# Akuaphonic_All_FIX.net
KiCad netlist of a schematic drawn in EAGLE
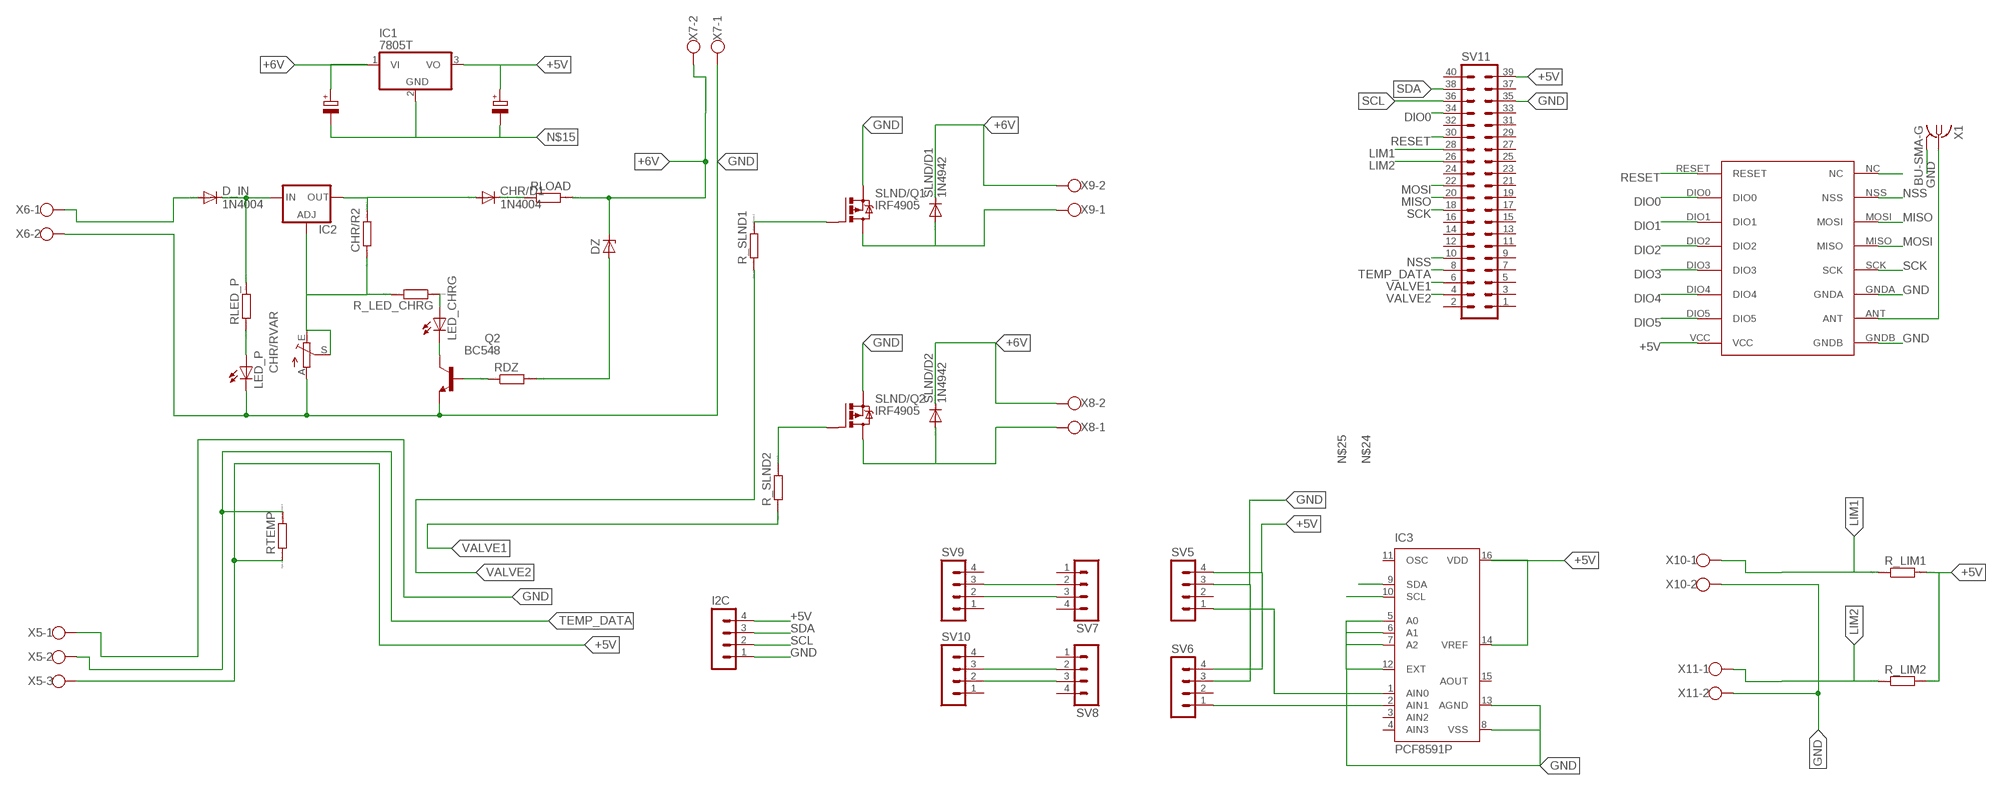
[diagram p0: schematic, sheet 1]

(export (version "E")
  (design (tool "Eeschema 10.0.6"))
  (components
    (comp (ref "CHR/D1")
      (value "1N4004")
      (footprint "eagle-import:DO41-10")
      (libsource (lib "eagle-import") (part "1N4004"))
    )
    (comp (ref "CHR/R2")
      (value "R0207/10")
      (footprint "eagle-import:0207_10")
      (libsource (lib "eagle-import") (part "R0207/10"))
    )
    (comp (ref "CHR/RVAR")
      (value "TRIM_EU-B25P")
      (footprint "eagle-import:B25P")
      (libsource (lib "eagle-import") (part "TRIM_EU-B25P"))
    )
    (comp (ref "DZ")
      (value "ZENER-DIODEDO35Z10")
      (footprint "eagle-import:DO35Z10")
      (libsource (lib "eagle-import") (part "ZENER-DIODEDO35Z10"))
    )
    (comp (ref "D_IN")
      (value "1N4004")
      (footprint "eagle-import:DO41-10")
      (libsource (lib "eagle-import") (part "1N4004"))
    )
    (comp (ref "I2C")
      (value "MA04-1")
      (footprint "eagle-import:MA04-1")
      (libsource (lib "eagle-import") (part "MA04-1"))
    )
    (comp (ref "IC1")
      (value "7805T")
      (footprint "eagle-import:TO220H")
      (libsource (lib "eagle-import") (part "78T05"))
    )
    (comp (ref "IC2")
      (value "LM317TL")
      (footprint "eagle-import:317TL")
      (libsource (lib "eagle-import") (part "LM317TL"))
    )
    (comp (ref "IC3")
      (value "PCF8591P")
      (footprint "eagle-import:DIL16")
      (fields (field (name "MF") "FARNELL"))
      (libsource (lib "eagle-import") (part "PCF8591P"))
    )
    (comp (ref "LED_CHRG")
      (value "LED3MM")
      (footprint "eagle-import:LED3MM")
      (libsource (lib "eagle-import") (part "LED3MM"))
    )
    (comp (ref "LED_P")
      (value "LED3MM")
      (footprint "eagle-import:LED3MM")
      (libsource (lib "eagle-import") (part "LED3MM"))
    )
    (comp (ref "Q2")
      (value "BC548")
      (footprint "eagle-import:TO92-EBC")
      (libsource (lib "eagle-import") (part "BC548"))
    )
    (comp (ref "RDZ")
      (value "R0207/10")
      (footprint "eagle-import:0207_10")
      (libsource (lib "eagle-import") (part "R0207/10"))
    )
    (comp (ref "RLED_P")
      (value "R0207/10")
      (footprint "eagle-import:0207_10")
      (libsource (lib "eagle-import") (part "R0207/10"))
    )
    (comp (ref "RLOAD")
      (value "R0207/10")
      (footprint "eagle-import:0207_10")
      (libsource (lib "eagle-import") (part "R0207/10"))
    )
    (comp (ref "RTEMP")
      (value "R0207/10")
      (footprint "eagle-import:0207_10")
      (libsource (lib "eagle-import") (part "R0207/10"))
    )
    (comp (ref "R_LED_CHRG")
      (value "R0207/10")
      (footprint "eagle-import:0207_10")
      (libsource (lib "eagle-import") (part "R0207/10"))
    )
    (comp (ref "R_LIM1")
      (value "R0207/10")
      (footprint "eagle-import:0207_10")
      (libsource (lib "eagle-import") (part "R0207/10"))
    )
    (comp (ref "R_LIM2")
      (value "R0207/10")
      (footprint "eagle-import:0207_10")
      (libsource (lib "eagle-import") (part "R0207/10"))
    )
    (comp (ref "R_SLND1")
      (value "R0207/10")
      (footprint "eagle-import:0207_10")
      (libsource (lib "eagle-import") (part "R0207/10"))
    )
    (comp (ref "R_SLND2")
      (value "R0207/10")
      (footprint "eagle-import:0207_10")
      (libsource (lib "eagle-import") (part "R0207/10"))
    )
    (comp (ref "SLND/D1")
      (value "1N4942")
      (footprint "eagle-import:DO41-10")
      (libsource (lib "eagle-import") (part "1N4942"))
    )
    (comp (ref "SLND/D2")
      (value "1N4942")
      (footprint "eagle-import:DO41-10")
      (libsource (lib "eagle-import") (part "1N4942"))
    )
    (comp (ref "SLND/Q1")
      (value "IRF4905")
      (footprint "eagle-import:TO220BH")
      (libsource (lib "eagle-import") (part "IRF4905"))
    )
    (comp (ref "SLND/Q2")
      (value "IRF4905")
      (footprint "eagle-import:TO220BH")
      (libsource (lib "eagle-import") (part "IRF4905"))
    )
    (comp (ref "SV5")
      (value "MA04-1")
      (footprint "eagle-import:MA04-1")
      (libsource (lib "eagle-import") (part "MA04-1"))
    )
    (comp (ref "SV6")
      (value "MA04-1")
      (footprint "eagle-import:MA04-1")
      (libsource (lib "eagle-import") (part "MA04-1"))
    )
    (comp (ref "SV7")
      (value "MA04-1")
      (footprint "eagle-import:MA04-1")
      (libsource (lib "eagle-import") (part "MA04-1"))
    )
    (comp (ref "SV8")
      (value "MA04-1")
      (footprint "eagle-import:MA04-1")
      (libsource (lib "eagle-import") (part "MA04-1"))
    )
    (comp (ref "SV9")
      (value "MA04-1")
      (footprint "eagle-import:MA04-1")
      (libsource (lib "eagle-import") (part "MA04-1"))
    )
    (comp (ref "SV10")
      (value "MA04-1")
      (footprint "eagle-import:MA04-1")
      (libsource (lib "eagle-import") (part "MA04-1"))
    )
    (comp (ref "SV11")
      (value "MA20-2")
      (footprint "eagle-import:MA20-2")
      (libsource (lib "eagle-import") (part "MA20-2"))
    )
    (comp (ref "U$1")
      (value "RFM69HW")
      (footprint "eagle-import:RFM")
      (libsource (lib "eagle-import") (part "RFM69HW"))
    )
    (comp (ref "X1")
      (value "BU-SMA-G")
      (footprint "eagle-import:BU-SMA-G")
      (libsource (lib "eagle-import") (part "BU-SMA-G"))
    )
    (comp (ref "X5")
      (value "W237-103")
      (footprint "eagle-import:W237-103")
      (fields (field (name "MPN") "237-103"))
      (libsource (lib "eagle-import") (part "W237-103"))
    )
    (comp (ref "X6")
      (value "W237-102")
      (footprint "eagle-import:W237-102")
      (fields (field (name "MPN") "237-102"))
      (libsource (lib "eagle-import") (part "W237-102"))
    )
    (comp (ref "X7")
      (value "W237-102")
      (footprint "eagle-import:W237-102")
      (fields (field (name "MPN") "237-102"))
      (libsource (lib "eagle-import") (part "W237-102"))
    )
    (comp (ref "X8")
      (value "W237-102")
      (footprint "eagle-import:W237-102")
      (fields (field (name "MPN") "237-102"))
      (libsource (lib "eagle-import") (part "W237-102"))
    )
    (comp (ref "X9")
      (value "W237-102")
      (footprint "eagle-import:W237-102")
      (fields (field (name "MPN") "237-102"))
      (libsource (lib "eagle-import") (part "W237-102"))
    )
    (comp (ref "X10")
      (value "W237-102")
      (footprint "eagle-import:W237-102")
      (fields (field (name "MPN") "237-102"))
      (libsource (lib "eagle-import") (part "W237-102"))
    )
    (comp (ref "X11")
      (value "W237-102")
      (footprint "eagle-import:W237-102")
      (fields (field (name "MPN") "237-102"))
      (libsource (lib "eagle-import") (part "W237-102"))
    )
  )
  (nets
    (net (code "1") (name "+5V") (class "Default")
      (node (ref "I2C") (pin "4") (pinfunction "4_4") (pintype "passive"))
      (node (ref "IC1") (pin "3") (pinfunction "VO_3") (pintype "passive"))
      (node (ref "IC3") (pin "14") (pinfunction "VREF_14") (pintype "input"))
      (node (ref "IC3") (pin "16") (pinfunction "VDD_16") (pintype "power_in"))
      (node (ref "RTEMP") (pin "1") (pinfunction "1_1") (pintype "passive"))
      (node (ref "R_LIM1") (pin "2") (pinfunction "2_2") (pintype "passive"))
      (node (ref "R_LIM2") (pin "2") (pinfunction "2_2") (pintype "passive"))
      (node (ref "SV11") (pin "39") (pinfunction "39_39") (pintype "passive"))
      (node (ref "SV5") (pin "4") (pinfunction "4_4") (pintype "passive"))
      (node (ref "SV6") (pin "4") (pinfunction "4_4") (pintype "passive"))
      (node (ref "U$1") (pin "VCC") (pinfunction "VCC_VCC") (pintype "bidirectional"))
      (node (ref "X5") (pin "3") (pinfunction "KL_3") (pintype "passive"))
    )
    (net (code "2") (name "+6V") (class "Default")
      (node (ref "DZ") (pin "C") (pinfunction "C_C") (pintype "passive"))
      (node (ref "IC1") (pin "1") (pinfunction "VI_1") (pintype "input"))
      (node (ref "RLOAD") (pin "2") (pinfunction "2_2") (pintype "passive"))
      (node (ref "SLND/D1") (pin "C") (pinfunction "C_C") (pintype "passive"))
      (node (ref "SLND/D2") (pin "C") (pinfunction "C_C") (pintype "passive"))
      (node (ref "X7") (pin "2") (pinfunction "KL_2") (pintype "passive"))
      (node (ref "X8") (pin "2") (pinfunction "KL_2") (pintype "passive"))
      (node (ref "X9") (pin "2") (pinfunction "KL_2") (pintype "passive"))
    )
    (net (code "3") (name "/DIO0") (class "Default")
      (node (ref "SV11") (pin "34") (pinfunction "34_34") (pintype "passive"))
      (node (ref "U$1") (pin "DIO0") (pinfunction "DIO0_DIO0") (pintype "bidirectional"))
    )
    (net (code "4") (name "/DIO1") (class "Default")
      (node (ref "U$1") (pin "DIO1") (pinfunction "DIO1_DIO1") (pintype "bidirectional"))
    )
    (net (code "5") (name "/DIO2") (class "Default")
      (node (ref "U$1") (pin "DIO2") (pinfunction "DIO2_DIO2") (pintype "bidirectional"))
    )
    (net (code "6") (name "/DIO3") (class "Default")
      (node (ref "U$1") (pin "DIO3") (pinfunction "DIO3_DIO3") (pintype "bidirectional"))
    )
    (net (code "7") (name "/DIO4") (class "Default")
      (node (ref "U$1") (pin "DIO4") (pinfunction "DIO4_DIO4") (pintype "bidirectional"))
    )
    (net (code "8") (name "/DIO5") (class "Default")
      (node (ref "U$1") (pin "DIO5") (pinfunction "DIO5_DIO5") (pintype "bidirectional"))
    )
    (net (code "9") (name "/MISO") (class "Default")
      (node (ref "SV11") (pin "20") (pinfunction "20_20") (pintype "passive"))
      (node (ref "U$1") (pin "MOSI") (pinfunction "MOSI_MOSI") (pintype "bidirectional"))
    )
    (net (code "10") (name "/MOSI") (class "Default")
      (node (ref "SV11") (pin "22") (pinfunction "22_22") (pintype "passive"))
      (node (ref "U$1") (pin "MISO") (pinfunction "MISO_MISO") (pintype "bidirectional"))
    )
    (net (code "11") (name "/N$24") (class "Default")
      (node (ref "IC3") (pin "9") (pinfunction "SDA_9") (pintype "bidirectional"))
    )
    (net (code "12") (name "/N$25") (class "Default")
      (node (ref "IC3") (pin "10") (pinfunction "SCL_10") (pintype "input"))
    )
    (net (code "13") (name "/NSS") (class "Default")
      (node (ref "SV11") (pin "10") (pinfunction "10_10") (pintype "passive"))
      (node (ref "U$1") (pin "NSS") (pinfunction "NSS_NSS") (pintype "bidirectional"))
    )
    (net (code "14") (name "/RESET") (class "Default")
      (node (ref "SV11") (pin "30") (pinfunction "30_30") (pintype "passive"))
      (node (ref "U$1") (pin "RESET") (pinfunction "RESET_RESET") (pintype "bidirectional"))
    )
    (net (code "15") (name "/SCK") (class "Default")
      (node (ref "SV11") (pin "18") (pinfunction "18_18") (pintype "passive"))
      (node (ref "U$1") (pin "SCK") (pinfunction "SCK_SCK") (pintype "bidirectional"))
    )
    (net (code "16") (name "GND") (class "Default")
      (node (ref "CHR/RVAR") (pin "A") (pinfunction "A_A") (pintype "passive"))
      (node (ref "I2C") (pin "1") (pinfunction "1_1") (pintype "passive"))
      (node (ref "IC3") (pin "12") (pinfunction "EXT_12") (pintype "input"))
      (node (ref "IC3") (pin "13") (pinfunction "AGND_13") (pintype "power_in"))
      (node (ref "IC3") (pin "5") (pinfunction "A0_5") (pintype "input"))
      (node (ref "IC3") (pin "6") (pinfunction "A1_6") (pintype "input"))
      (node (ref "IC3") (pin "7") (pinfunction "A2_7") (pintype "input"))
      (node (ref "IC3") (pin "8") (pinfunction "VSS_8") (pintype "power_in"))
      (node (ref "LED_P") (pin "K") (pinfunction "C_K") (pintype "passive"))
      (node (ref "Q2") (pin "E") (pinfunction "E_E") (pintype "passive"))
      (node (ref "SLND/Q1") (pin "S") (pinfunction "S_S") (pintype "passive"))
      (node (ref "SLND/Q2") (pin "S") (pinfunction "S_S") (pintype "passive"))
      (node (ref "SV11") (pin "35") (pinfunction "35_35") (pintype "passive"))
      (node (ref "SV5") (pin "3") (pinfunction "3_3") (pintype "passive"))
      (node (ref "SV6") (pin "3") (pinfunction "3_3") (pintype "passive"))
      (node (ref "U$1") (pin "GNDA") (pinfunction "GNDA_GNDA") (pintype "bidirectional"))
      (node (ref "U$1") (pin "GNDB") (pinfunction "GNDB_GNDB") (pintype "bidirectional"))
      (node (ref "X1") (pin "2") (pinfunction "2_2") (pintype "passive"))
      (node (ref "X1") (pin "3") (pinfunction "2_3") (pintype "passive"))
      (node (ref "X1") (pin "4") (pinfunction "2_4") (pintype "passive"))
      (node (ref "X1") (pin "5") (pinfunction "2_5") (pintype "passive"))
      (node (ref "X10") (pin "2") (pinfunction "KL_2") (pintype "passive"))
      (node (ref "X11") (pin "2") (pinfunction "KL_2") (pintype "passive"))
      (node (ref "X5") (pin "1") (pinfunction "KL_1") (pintype "passive"))
      (node (ref "X6") (pin "2") (pinfunction "KL_2") (pintype "passive"))
      (node (ref "X7") (pin "1") (pinfunction "KL_1") (pintype "passive"))
    )
    (net (code "17") (name "LIM1") (class "Default")
      (node (ref "R_LIM1") (pin "1") (pinfunction "1_1") (pintype "passive"))
      (node (ref "SV11") (pin "28") (pinfunction "28_28") (pintype "passive"))
      (node (ref "X10") (pin "1") (pinfunction "KL_1") (pintype "passive"))
    )
    (net (code "18") (name "LIM2") (class "Default")
      (node (ref "R_LIM2") (pin "1") (pinfunction "1_1") (pintype "passive"))
      (node (ref "SV11") (pin "26") (pinfunction "26_26") (pintype "passive"))
      (node (ref "X11") (pin "1") (pinfunction "KL_1") (pintype "passive"))
    )
    (net (code "19") (name "N$15") (class "Default")
      (node (ref "IC1") (pin "2") (pinfunction "GND_2") (pintype "passive"))
    )
    (net (code "20") (name "Net-(CHR/D1-PadC)") (class "Default")
      (node (ref "CHR/D1") (pin "C") (pinfunction "C_C") (pintype "passive"))
      (node (ref "RLOAD") (pin "1") (pinfunction "1_1") (pintype "passive"))
    )
    (net (code "21") (name "Net-(DZ-PadA)") (class "Default")
      (node (ref "DZ") (pin "A") (pinfunction "A_A") (pintype "passive"))
      (node (ref "RDZ") (pin "2") (pinfunction "2_2") (pintype "passive"))
    )
    (net (code "22") (name "Net-(IC2-ADJ)") (class "Default")
      (node (ref "CHR/R2") (pin "1") (pinfunction "1_1") (pintype "passive"))
      (node (ref "CHR/RVAR") (pin "E") (pinfunction "E_E") (pintype "passive"))
      (node (ref "CHR/RVAR") (pin "S") (pinfunction "S_S") (pintype "passive"))
      (node (ref "IC2") (pin "1") (pinfunction "ADJ_1") (pintype "input"))
      (node (ref "R_LED_CHRG") (pin "2") (pinfunction "2_2") (pintype "passive"))
    )
    (net (code "23") (name "Net-(IC2-IN)") (class "Default")
      (node (ref "D_IN") (pin "C") (pinfunction "C_C") (pintype "passive"))
      (node (ref "IC2") (pin "3") (pinfunction "IN_3") (pintype "input"))
      (node (ref "RLED_P") (pin "2") (pinfunction "2_2") (pintype "passive"))
    )
    (net (code "24") (name "Net-(IC2-OUT)") (class "Default")
      (node (ref "CHR/D1") (pin "A") (pinfunction "A_A") (pintype "passive"))
      (node (ref "CHR/R2") (pin "2") (pinfunction "2_2") (pintype "passive"))
      (node (ref "IC2") (pin "2") (pinfunction "OUT_2") (pintype "passive"))
    )
    (net (code "25") (name "Net-(IC3-AIN0)") (class "Default")
      (node (ref "IC3") (pin "1") (pinfunction "AIN0_1") (pintype "input"))
      (node (ref "SV5") (pin "1") (pinfunction "1_1") (pintype "passive"))
    )
    (net (code "26") (name "Net-(IC3-AIN1)") (class "Default")
      (node (ref "IC3") (pin "2") (pinfunction "AIN1_2") (pintype "input"))
      (node (ref "SV6") (pin "1") (pinfunction "1_1") (pintype "passive"))
    )
    (net (code "27") (name "Net-(LED_CHRG-C)") (class "Default")
      (node (ref "LED_CHRG") (pin "K") (pinfunction "C_K") (pintype "passive"))
      (node (ref "Q2") (pin "C") (pinfunction "C_C") (pintype "passive"))
    )
    (net (code "28") (name "Net-(LED_CHRG-PadA)") (class "Default")
      (node (ref "LED_CHRG") (pin "A") (pinfunction "A_A") (pintype "passive"))
      (node (ref "R_LED_CHRG") (pin "1") (pinfunction "1_1") (pintype "passive"))
    )
    (net (code "29") (name "Net-(LED_P-PadA)") (class "Default")
      (node (ref "LED_P") (pin "A") (pinfunction "A_A") (pintype "passive"))
      (node (ref "RLED_P") (pin "1") (pinfunction "1_1") (pintype "passive"))
    )
    (net (code "30") (name "Net-(Q2-PadB)") (class "Default")
      (node (ref "Q2") (pin "B") (pinfunction "B_B") (pintype "passive"))
      (node (ref "RDZ") (pin "1") (pinfunction "1_1") (pintype "passive"))
    )
    (net (code "31") (name "Net-(R_SLND1-Pad2)") (class "Default")
      (node (ref "R_SLND1") (pin "2") (pinfunction "2_2") (pintype "passive"))
      (node (ref "SLND/Q1") (pin "G") (pinfunction "G_G") (pintype "passive"))
    )
    (net (code "32") (name "Net-(R_SLND2-Pad2)") (class "Default")
      (node (ref "R_SLND2") (pin "2") (pinfunction "2_2") (pintype "passive"))
      (node (ref "SLND/Q2") (pin "G") (pinfunction "G_G") (pintype "passive"))
    )
    (net (code "33") (name "Net-(SV7-Pad2)") (class "Default")
      (node (ref "SV7") (pin "2") (pinfunction "2_2") (pintype "passive"))
      (node (ref "SV9") (pin "3") (pinfunction "3_3") (pintype "passive"))
    )
    (net (code "34") (name "Net-(SV7-Pad3)") (class "Default")
      (node (ref "SV7") (pin "3") (pinfunction "3_3") (pintype "passive"))
      (node (ref "SV9") (pin "2") (pinfunction "2_2") (pintype "passive"))
    )
    (net (code "35") (name "Net-(SV10-Pad2)") (class "Default")
      (node (ref "SV10") (pin "2") (pinfunction "2_2") (pintype "passive"))
      (node (ref "SV8") (pin "3") (pinfunction "3_3") (pintype "passive"))
    )
    (net (code "36") (name "Net-(SV10-Pad3)") (class "Default")
      (node (ref "SV10") (pin "3") (pinfunction "3_3") (pintype "passive"))
      (node (ref "SV8") (pin "2") (pinfunction "2_2") (pintype "passive"))
    )
    (net (code "37") (name "Net-(U$1-PadANT)") (class "Default")
      (node (ref "U$1") (pin "ANT") (pinfunction "ANT_ANT") (pintype "bidirectional"))
      (node (ref "X1") (pin "1") (pinfunction "1_1") (pintype "passive"))
    )
    (net (code "38") (name "Net-(X6A-KL)") (class "Default")
      (node (ref "D_IN") (pin "A") (pinfunction "A_A") (pintype "passive"))
      (node (ref "X6") (pin "1") (pinfunction "KL_1") (pintype "passive"))
    )
    (net (code "39") (name "Net-(X8A-KL)") (class "Default")
      (node (ref "SLND/D2") (pin "A") (pinfunction "A_A") (pintype "passive"))
      (node (ref "SLND/Q2") (pin "D") (pinfunction "D_D") (pintype "passive"))
      (node (ref "X8") (pin "1") (pinfunction "KL_1") (pintype "passive"))
    )
    (net (code "40") (name "Net-(X9A-KL)") (class "Default")
      (node (ref "SLND/D1") (pin "A") (pinfunction "A_A") (pintype "passive"))
      (node (ref "SLND/Q1") (pin "D") (pinfunction "D_D") (pintype "passive"))
      (node (ref "X9") (pin "1") (pinfunction "KL_1") (pintype "passive"))
    )
    (net (code "41") (name "SCL") (class "Default")
      (node (ref "I2C") (pin "2") (pinfunction "2_2") (pintype "passive"))
      (node (ref "SV11") (pin "36") (pinfunction "36_36") (pintype "passive"))
    )
    (net (code "42") (name "SDA") (class "Default")
      (node (ref "I2C") (pin "3") (pinfunction "3_3") (pintype "passive"))
      (node (ref "SV11") (pin "38") (pinfunction "38_38") (pintype "passive"))
    )
    (net (code "43") (name "TEMP_DATA") (class "Default")
      (node (ref "RTEMP") (pin "2") (pinfunction "2_2") (pintype "passive"))
      (node (ref "SV11") (pin "8") (pinfunction "8_8") (pintype "passive"))
      (node (ref "X5") (pin "2") (pinfunction "KL_2") (pintype "passive"))
    )
    (net (code "44") (name "VALVE1") (class "Default")
      (node (ref "R_SLND2") (pin "1") (pinfunction "1_1") (pintype "passive"))
      (node (ref "SV11") (pin "6") (pinfunction "6_6") (pintype "passive"))
    )
    (net (code "45") (name "VALVE2") (class "Default")
      (node (ref "R_SLND1") (pin "1") (pinfunction "1_1") (pintype "passive"))
      (node (ref "SV11") (pin "4") (pinfunction "4_4") (pintype "passive"))
    )
    (net (code "46") (name "unconnected-(IC3-AIN2-Pad3)") (class "Default")
      (node (ref "IC3") (pin "3") (pinfunction "AIN2_3") (pintype "input"))
    )
    (net (code "47") (name "unconnected-(IC3-AIN3-Pad4)") (class "Default")
      (node (ref "IC3") (pin "4") (pinfunction "AIN3_4") (pintype "input"))
    )
    (net (code "48") (name "unconnected-(IC3-AOUT-Pad15)") (class "Default")
      (node (ref "IC3") (pin "15") (pinfunction "AOUT_15") (pintype "output"))
    )
    (net (code "49") (name "unconnected-(IC3-OSC-Pad11)") (class "Default")
      (node (ref "IC3") (pin "11") (pinfunction "OSC_11") (pintype "input"))
    )
    (net (code "50") (name "unconnected-(SV5-Pad2)") (class "Default")
      (node (ref "SV5") (pin "2") (pinfunction "2_2") (pintype "passive"))
    )
    (net (code "51") (name "unconnected-(SV6-Pad2)") (class "Default")
      (node (ref "SV6") (pin "2") (pinfunction "2_2") (pintype "passive"))
    )
    (net (code "52") (name "unconnected-(SV7-Pad1)") (class "Default")
      (node (ref "SV7") (pin "1") (pinfunction "1_1") (pintype "passive"))
    )
    (net (code "53") (name "unconnected-(SV7-Pad4)") (class "Default")
      (node (ref "SV7") (pin "4") (pinfunction "4_4") (pintype "passive"))
    )
    (net (code "54") (name "unconnected-(SV8-Pad1)") (class "Default")
      (node (ref "SV8") (pin "1") (pinfunction "1_1") (pintype "passive"))
    )
    (net (code "55") (name "unconnected-(SV8-Pad4)") (class "Default")
      (node (ref "SV8") (pin "4") (pinfunction "4_4") (pintype "passive"))
    )
    (net (code "56") (name "unconnected-(SV9-Pad1)") (class "Default")
      (node (ref "SV9") (pin "1") (pinfunction "1_1") (pintype "passive"))
    )
    (net (code "57") (name "unconnected-(SV9-Pad4)") (class "Default")
      (node (ref "SV9") (pin "4") (pinfunction "4_4") (pintype "passive"))
    )
    (net (code "58") (name "unconnected-(SV10-Pad1)") (class "Default")
      (node (ref "SV10") (pin "1") (pinfunction "1_1") (pintype "passive"))
    )
    (net (code "59") (name "unconnected-(SV10-Pad4)") (class "Default")
      (node (ref "SV10") (pin "4") (pinfunction "4_4") (pintype "passive"))
    )
    (net (code "60") (name "unconnected-(SV11-Pad1)") (class "Default")
      (node (ref "SV11") (pin "1") (pinfunction "1_1") (pintype "passive"))
    )
    (net (code "61") (name "unconnected-(SV11-Pad2)") (class "Default")
      (node (ref "SV11") (pin "2") (pinfunction "2_2") (pintype "passive"))
    )
    (net (code "62") (name "unconnected-(SV11-Pad3)") (class "Default")
      (node (ref "SV11") (pin "3") (pinfunction "3_3") (pintype "passive"))
    )
    (net (code "63") (name "unconnected-(SV11-Pad5)") (class "Default")
      (node (ref "SV11") (pin "5") (pinfunction "5_5") (pintype "passive"))
    )
    (net (code "64") (name "unconnected-(SV11-Pad7)") (class "Default")
      (node (ref "SV11") (pin "7") (pinfunction "7_7") (pintype "passive"))
    )
    (net (code "65") (name "unconnected-(SV11-Pad9)") (class "Default")
      (node (ref "SV11") (pin "9") (pinfunction "9_9") (pintype "passive"))
    )
    (net (code "66") (name "unconnected-(SV11-Pad11)") (class "Default")
      (node (ref "SV11") (pin "11") (pinfunction "11_11") (pintype "passive"))
    )
    (net (code "67") (name "unconnected-(SV11-Pad12)") (class "Default")
      (node (ref "SV11") (pin "12") (pinfunction "12_12") (pintype "passive"))
    )
    (net (code "68") (name "unconnected-(SV11-Pad13)") (class "Default")
      (node (ref "SV11") (pin "13") (pinfunction "13_13") (pintype "passive"))
    )
    (net (code "69") (name "unconnected-(SV11-Pad14)") (class "Default")
      (node (ref "SV11") (pin "14") (pinfunction "14_14") (pintype "passive"))
    )
    (net (code "70") (name "unconnected-(SV11-Pad15)") (class "Default")
      (node (ref "SV11") (pin "15") (pinfunction "15_15") (pintype "passive"))
    )
    (net (code "71") (name "unconnected-(SV11-Pad16)") (class "Default")
      (node (ref "SV11") (pin "16") (pinfunction "16_16") (pintype "passive"))
    )
    (net (code "72") (name "unconnected-(SV11-Pad17)") (class "Default")
      (node (ref "SV11") (pin "17") (pinfunction "17_17") (pintype "passive"))
    )
    (net (code "73") (name "unconnected-(SV11-Pad19)") (class "Default")
      (node (ref "SV11") (pin "19") (pinfunction "19_19") (pintype "passive"))
    )
    (net (code "74") (name "unconnected-(SV11-Pad21)") (class "Default")
      (node (ref "SV11") (pin "21") (pinfunction "21_21") (pintype "passive"))
    )
    (net (code "75") (name "unconnected-(SV11-Pad23)") (class "Default")
      (node (ref "SV11") (pin "23") (pinfunction "23_23") (pintype "passive"))
    )
    (net (code "76") (name "unconnected-(SV11-Pad24)") (class "Default")
      (node (ref "SV11") (pin "24") (pinfunction "24_24") (pintype "passive"))
    )
    (net (code "77") (name "unconnected-(SV11-Pad25)") (class "Default")
      (node (ref "SV11") (pin "25") (pinfunction "25_25") (pintype "passive"))
    )
    (net (code "78") (name "unconnected-(SV11-Pad27)") (class "Default")
      (node (ref "SV11") (pin "27") (pinfunction "27_27") (pintype "passive"))
    )
    (net (code "79") (name "unconnected-(SV11-Pad29)") (class "Default")
      (node (ref "SV11") (pin "29") (pinfunction "29_29") (pintype "passive"))
    )
    (net (code "80") (name "unconnected-(SV11-Pad31)") (class "Default")
      (node (ref "SV11") (pin "31") (pinfunction "31_31") (pintype "passive"))
    )
    (net (code "81") (name "unconnected-(SV11-Pad32)") (class "Default")
      (node (ref "SV11") (pin "32") (pinfunction "32_32") (pintype "passive"))
    )
    (net (code "82") (name "unconnected-(SV11-Pad33)") (class "Default")
      (node (ref "SV11") (pin "33") (pinfunction "33_33") (pintype "passive"))
    )
    (net (code "83") (name "unconnected-(SV11-Pad37)") (class "Default")
      (node (ref "SV11") (pin "37") (pinfunction "37_37") (pintype "passive"))
    )
    (net (code "84") (name "unconnected-(SV11-Pad40)") (class "Default")
      (node (ref "SV11") (pin "40") (pinfunction "40_40") (pintype "passive"))
    )
    (net (code "85") (name "unconnected-(U$1-PadNC)") (class "Default")
      (node (ref "U$1") (pin "NC") (pinfunction "NC_NC") (pintype "bidirectional"))
    )
  )
)
